# Ultrasonic_sensor_switch.net
KiCad netlist of a schematic drawn in EAGLE
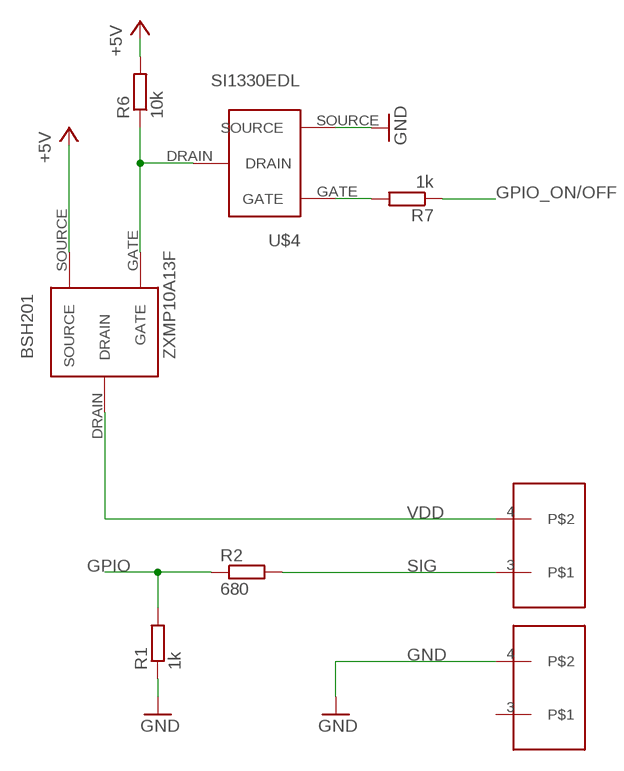
[diagram p0: schematic, sheet 1]

(export (version "E")
  (design (tool "Eeschema 10.0.6"))
  (components
    (comp (ref "BSH201")
      (value "ZXMP10A13F")
      (footprint "eagle-import:P-CHANNEL")
      (libsource (lib "eagle-import") (part "ZXMP10A13F"))
    )
    (comp (ref "R1")
      (value "1k")
      (footprint "eagle-import:R0805")
      (libsource (lib "eagle-import") (part "R-EU_R0805"))
    )
    (comp (ref "R2")
      (value "680")
      (footprint "eagle-import:R0805")
      (libsource (lib "eagle-import") (part "R-EU_R0805"))
    )
    (comp (ref "R6")
      (value "10k")
      (footprint "eagle-import:R0805")
      (libsource (lib "eagle-import") (part "R-EU_R0805"))
    )
    (comp (ref "R7")
      (value "1k")
      (footprint "eagle-import:R0805")
      (libsource (lib "eagle-import") (part "R-EU_R0805"))
    )
    (comp (ref "SKRUVPLINT_2P1")
      (value "SKRUVPLINT_2P")
      (footprint "eagle-import:SKRUVPLINT_2P")
      (libsource (lib "eagle-import") (part "SKRUVPLINT_2P"))
    )
    (comp (ref "SKRUVPLINT_2P2")
      (value "SKRUVPLINT_2P")
      (footprint "eagle-import:SKRUVPLINT_2P")
      (libsource (lib "eagle-import") (part "SKRUVPLINT_2P"))
    )
    (comp (ref "U$4")
      (value "SI1330EDL")
      (footprint "eagle-import:SOT-323")
      (libsource (lib "eagle-import") (part "SI1330EDL"))
    )
  )
  (nets
    (net (code "1") (name "+5V") (class "Default")
      (node (ref "BSH201") (pin "SOURCE") (pinfunction "SOURCE_SOURCE") (pintype "bidirectional"))
      (node (ref "R6") (pin "2") (pinfunction "2_2") (pintype "passive"))
    )
    (net (code "2") (name "/GPIO") (class "Default")
      (node (ref "R1") (pin "2") (pinfunction "2_2") (pintype "passive"))
      (node (ref "R2") (pin "1") (pinfunction "1_1") (pintype "passive"))
    )
    (net (code "3") (name "/GPIO_ON{slash}OFF") (class "Default")
      (node (ref "R7") (pin "1") (pinfunction "1_1") (pintype "passive"))
    )
    (net (code "4") (name "/SIG") (class "Default")
      (node (ref "R2") (pin "2") (pinfunction "2_2") (pintype "passive"))
      (node (ref "SKRUVPLINT_2P1") (pin "3") (pinfunction "P$1_3") (pintype "bidirectional"))
    )
    (net (code "5") (name "/VDD") (class "Default")
      (node (ref "BSH201") (pin "DRAIN") (pinfunction "DRAIN_DRAIN") (pintype "bidirectional"))
      (node (ref "SKRUVPLINT_2P1") (pin "4") (pinfunction "P$2_4") (pintype "bidirectional"))
    )
    (net (code "6") (name "GND") (class "Default")
      (node (ref "R1") (pin "1") (pinfunction "1_1") (pintype "passive"))
      (node (ref "SKRUVPLINT_2P2") (pin "4") (pinfunction "P$2_4") (pintype "bidirectional"))
      (node (ref "U$4") (pin "SOURCE") (pinfunction "SOURCE_SOURCE") (pintype "bidirectional"))
    )
    (net (code "7") (name "Net-(BSH201-PadGATE)") (class "Default")
      (node (ref "BSH201") (pin "GATE") (pinfunction "GATE_GATE") (pintype "bidirectional"))
      (node (ref "R6") (pin "1") (pinfunction "1_1") (pintype "passive"))
      (node (ref "U$4") (pin "DRAIN") (pinfunction "DRAIN_DRAIN") (pintype "bidirectional"))
    )
    (net (code "8") (name "Net-(R7-Pad2)") (class "Default")
      (node (ref "R7") (pin "2") (pinfunction "2_2") (pintype "passive"))
      (node (ref "U$4") (pin "GATE") (pinfunction "GATE_GATE") (pintype "bidirectional"))
    )
    (net (code "9") (name "unconnected-(SKRUVPLINT_2P2-P$1-Pad3)") (class "Default")
      (node (ref "SKRUVPLINT_2P2") (pin "3") (pinfunction "P$1_3") (pintype "bidirectional"))
    )
  )
)
